# Sch.net
KiCad netlist of a schematic drawn in Altium Designer
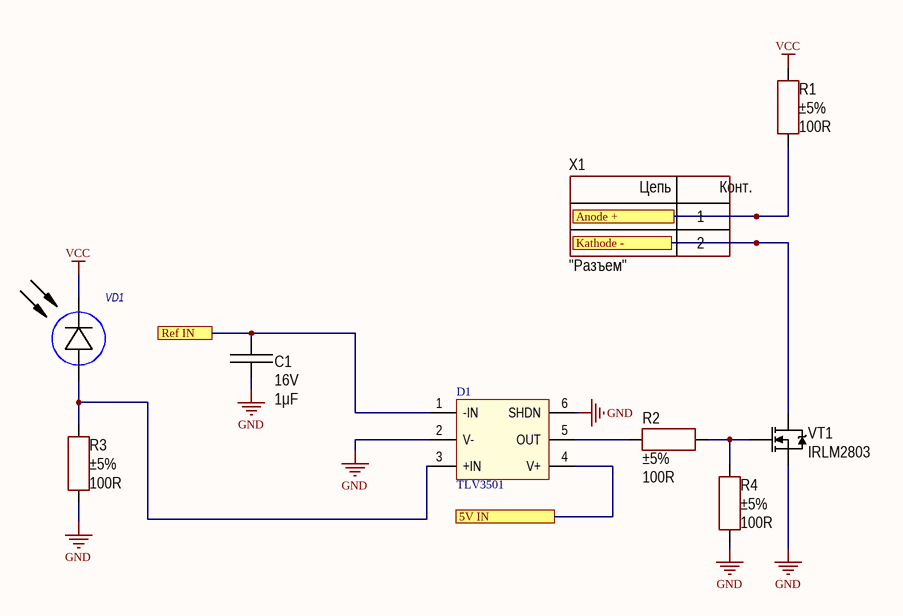
[diagram p0: Sch.SchDoc]

(export (version "E")
  (design (tool "Eeschema 10.0.6"))
  (components
    (comp (ref "C1")
      (value "1μF")
      (footprint "CAP: 0805")
      (fields
        (field (name "MANUFACTURER") "Yageo")
        (field (name "PARTNUMBER") "CC0805KRX7R7BB104")
        (field (name "VALUEMANUFACTURERPARTNUMBER") "Ceramic capacitor, 1μF, X7R, ±10%, 16V, 0805, -55...+125°C")
        (field (name "VOLTAGE") "16V")
      )
      (libsource (lib "capacitor") (part "Ceramic_0805"))
    )
    (comp (ref "D1")
      (value "TLV3501")
      (footprint "SOT23-6")
      (libsource (lib "ic-comparator") (part "TLV3501"))
    )
    (comp (ref "R1")
      (value "100R")
      (footprint "RES: 1206")
      (fields
        (field (name "MANUFACTURER") "Yageo")
        (field (name "PARTNUMBER") "RC1206JR-07100RL")
        (field (name "VALUEMANUFACTURERPARTNUMBER") "Resistor film, 100R, ±5%, 1206, 0.25W, -55...+125°C")
        (field (name "TOLERANCE") "±5%")
      )
      (libsource (lib "resistor") (part "Resistor_1206"))
    )
    (comp (ref "R2")
      (value "100R")
      (footprint "RES: 0805")
      (fields
        (field (name "MANUFACTURER") "Yageo")
        (field (name "PARTNUMBER") "RC0805JR-07100RL")
        (field (name "VALUEMANUFACTURERPARTNUMBER") "Resistor film, 100R, ±5%, 0805, 0.125W, -55...+125°C")
        (field (name "TOLERANCE") "±5%")
      )
      (libsource (lib "resistor") (part "Resistor_0805"))
    )
    (comp (ref "R3")
      (value "100R")
      (footprint "RES: 0805")
      (fields
        (field (name "MANUFACTURER") "Yageo")
        (field (name "PARTNUMBER") "RC0805JR-07100RL")
        (field (name "VALUEMANUFACTURERPARTNUMBER") "Resistor film, 100R, ±5%, 0805, 0.125W, -55...+125°C")
        (field (name "TOLERANCE") "±5%")
      )
      (libsource (lib "") (part "Resistor_0805_1"))
    )
    (comp (ref "R4")
      (value "100R")
      (footprint "RES: 0805")
      (fields
        (field (name "MANUFACTURER") "Yageo")
        (field (name "PARTNUMBER") "RC0805JR-07100RL")
        (field (name "VALUEMANUFACTURERPARTNUMBER") "Resistor film, 100R, ±5%, 0805, 0.125W, -55...+125°C")
        (field (name "TOLERANCE") "±5%")
      )
      (libsource (lib "") (part "Resistor_0805_1"))
    )
    (comp (ref "VD1") (value "SHF250") (footprint "LED: SFH757") (libsource (lib "diode") (part "SHF250")))
    (comp (ref "VT1")
      (value "~")
      (footprint "SOT23")
      (fields
        (field (name "MANUFACTURER") "Infineon Technologies")
        (field (name "VALUEMANUFACTURERPARTNUMBER") "MOSFET N-channel transistor, 80V, 7A, 9.1nC, 2.5W, 34mOhm, 756pF, 8-TDSON, -55...+150°C")
        (field (name "PARTNUMBER") "IRLM2803")
      )
      (libsource (lib "transistor") (part "MOSFET_N_132"))
    )
    (comp (ref "X1")
      (value "~")
      (footprint "CON: KF301-5.0-2P")
      (fields
        (field (name "MANUFACTURER") "Degson")
        (field (name "VALUEMANUFACTURERPARTNUMBER") "Terminal connector, 2pin, 3.5mm, 300VAC, 10A")
        (field (name "PARTNUMBER") "DG350-3.5-02P-14")
        (field (name "COMMENTTEXT") "\"Разъем\"")
      )
      (libsource (lib "connector") (part "Connector_terminal_2pin"))
    )
  )
  (nets
    (net (code "1") (name "/5V IN") (class "Default")
      (node (ref "D1") (pin "4") (pinfunction "V+_4") (pintype "passive"))
    )
    (net (code "2") (name "/Anode +") (class "Default")
      (node (ref "R1") (pin "1") (pinfunction "1_1") (pintype "passive"))
      (node (ref "X1") (pin "1") (pinfunction "1_1") (pintype "passive"))
    )
    (net (code "3") (name "/Kathode -") (class "Default")
      (node (ref "VT1") (pin "3") (pinfunction "D_3") (pintype "passive"))
      (node (ref "X1") (pin "2") (pinfunction "2_2") (pintype "passive"))
    )
    (net (code "4") (name "/Ref IN") (class "Default")
      (node (ref "C1") (pin "2") (pinfunction "2_2") (pintype "passive"))
      (node (ref "D1") (pin "1") (pinfunction "-IN_1") (pintype "passive"))
    )
    (net (code "5") (name "GND") (class "Default")
      (node (ref "C1") (pin "1") (pinfunction "1_1") (pintype "passive"))
      (node (ref "D1") (pin "2") (pinfunction "V-_2") (pintype "passive"))
      (node (ref "D1") (pin "6") (pinfunction "SHDN_6") (pintype "passive"))
      (node (ref "R3") (pin "1") (pinfunction "1_1") (pintype "passive"))
      (node (ref "R4") (pin "1") (pinfunction "1_1") (pintype "passive"))
      (node (ref "VT1") (pin "2") (pinfunction "S_2") (pintype "passive"))
    )
    (net (code "6") (name "Net-(D1-+IN)") (class "Default")
      (node (ref "D1") (pin "3") (pinfunction "+IN_3") (pintype "passive"))
      (node (ref "R3") (pin "2") (pinfunction "2_2") (pintype "passive"))
      (node (ref "VD1") (pin "1") (pinfunction "A_1") (pintype "passive"))
    )
    (net (code "7") (name "Net-(D1-OUT)") (class "Default")
      (node (ref "D1") (pin "5") (pinfunction "OUT_5") (pintype "passive"))
      (node (ref "R2") (pin "1") (pinfunction "1_1") (pintype "passive"))
    )
    (net (code "8") (name "Net-(VT1-G)") (class "Default")
      (node (ref "R2") (pin "2") (pinfunction "2_2") (pintype "passive"))
      (node (ref "R4") (pin "2") (pinfunction "2_2") (pintype "passive"))
      (node (ref "VT1") (pin "1") (pinfunction "G_1") (pintype "passive"))
    )
    (net (code "9") (name "VCC") (class "Default")
      (node (ref "R1") (pin "2") (pinfunction "2_2") (pintype "passive"))
      (node (ref "VD1") (pin "2") (pinfunction "C_2") (pintype "passive"))
    )
  )
)
